# glowbs_5.net
KiCad netlist of a schematic drawn in EAGLE
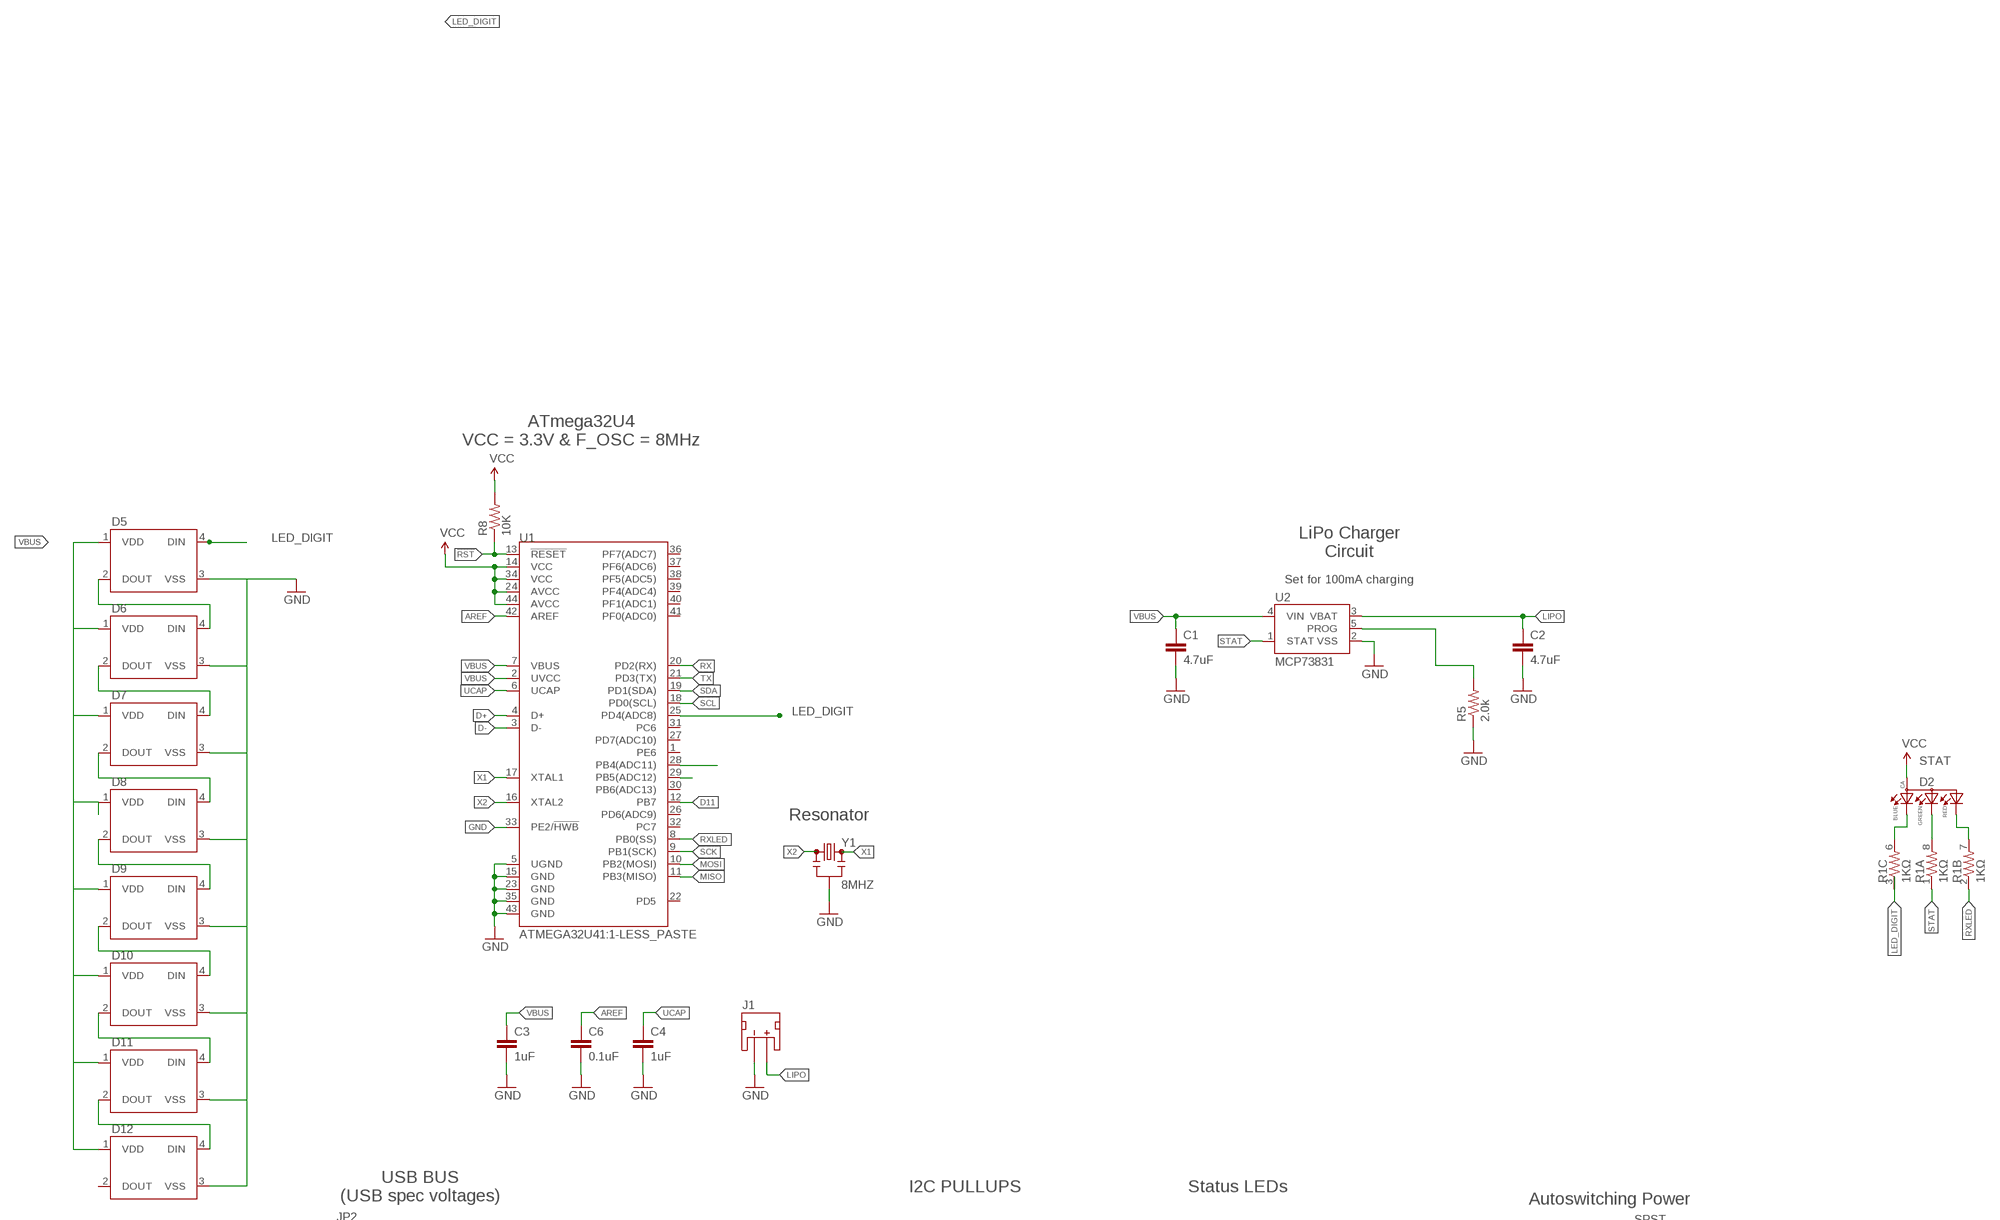
[diagram p0: schematic, sheet 1, part 1 of 2]
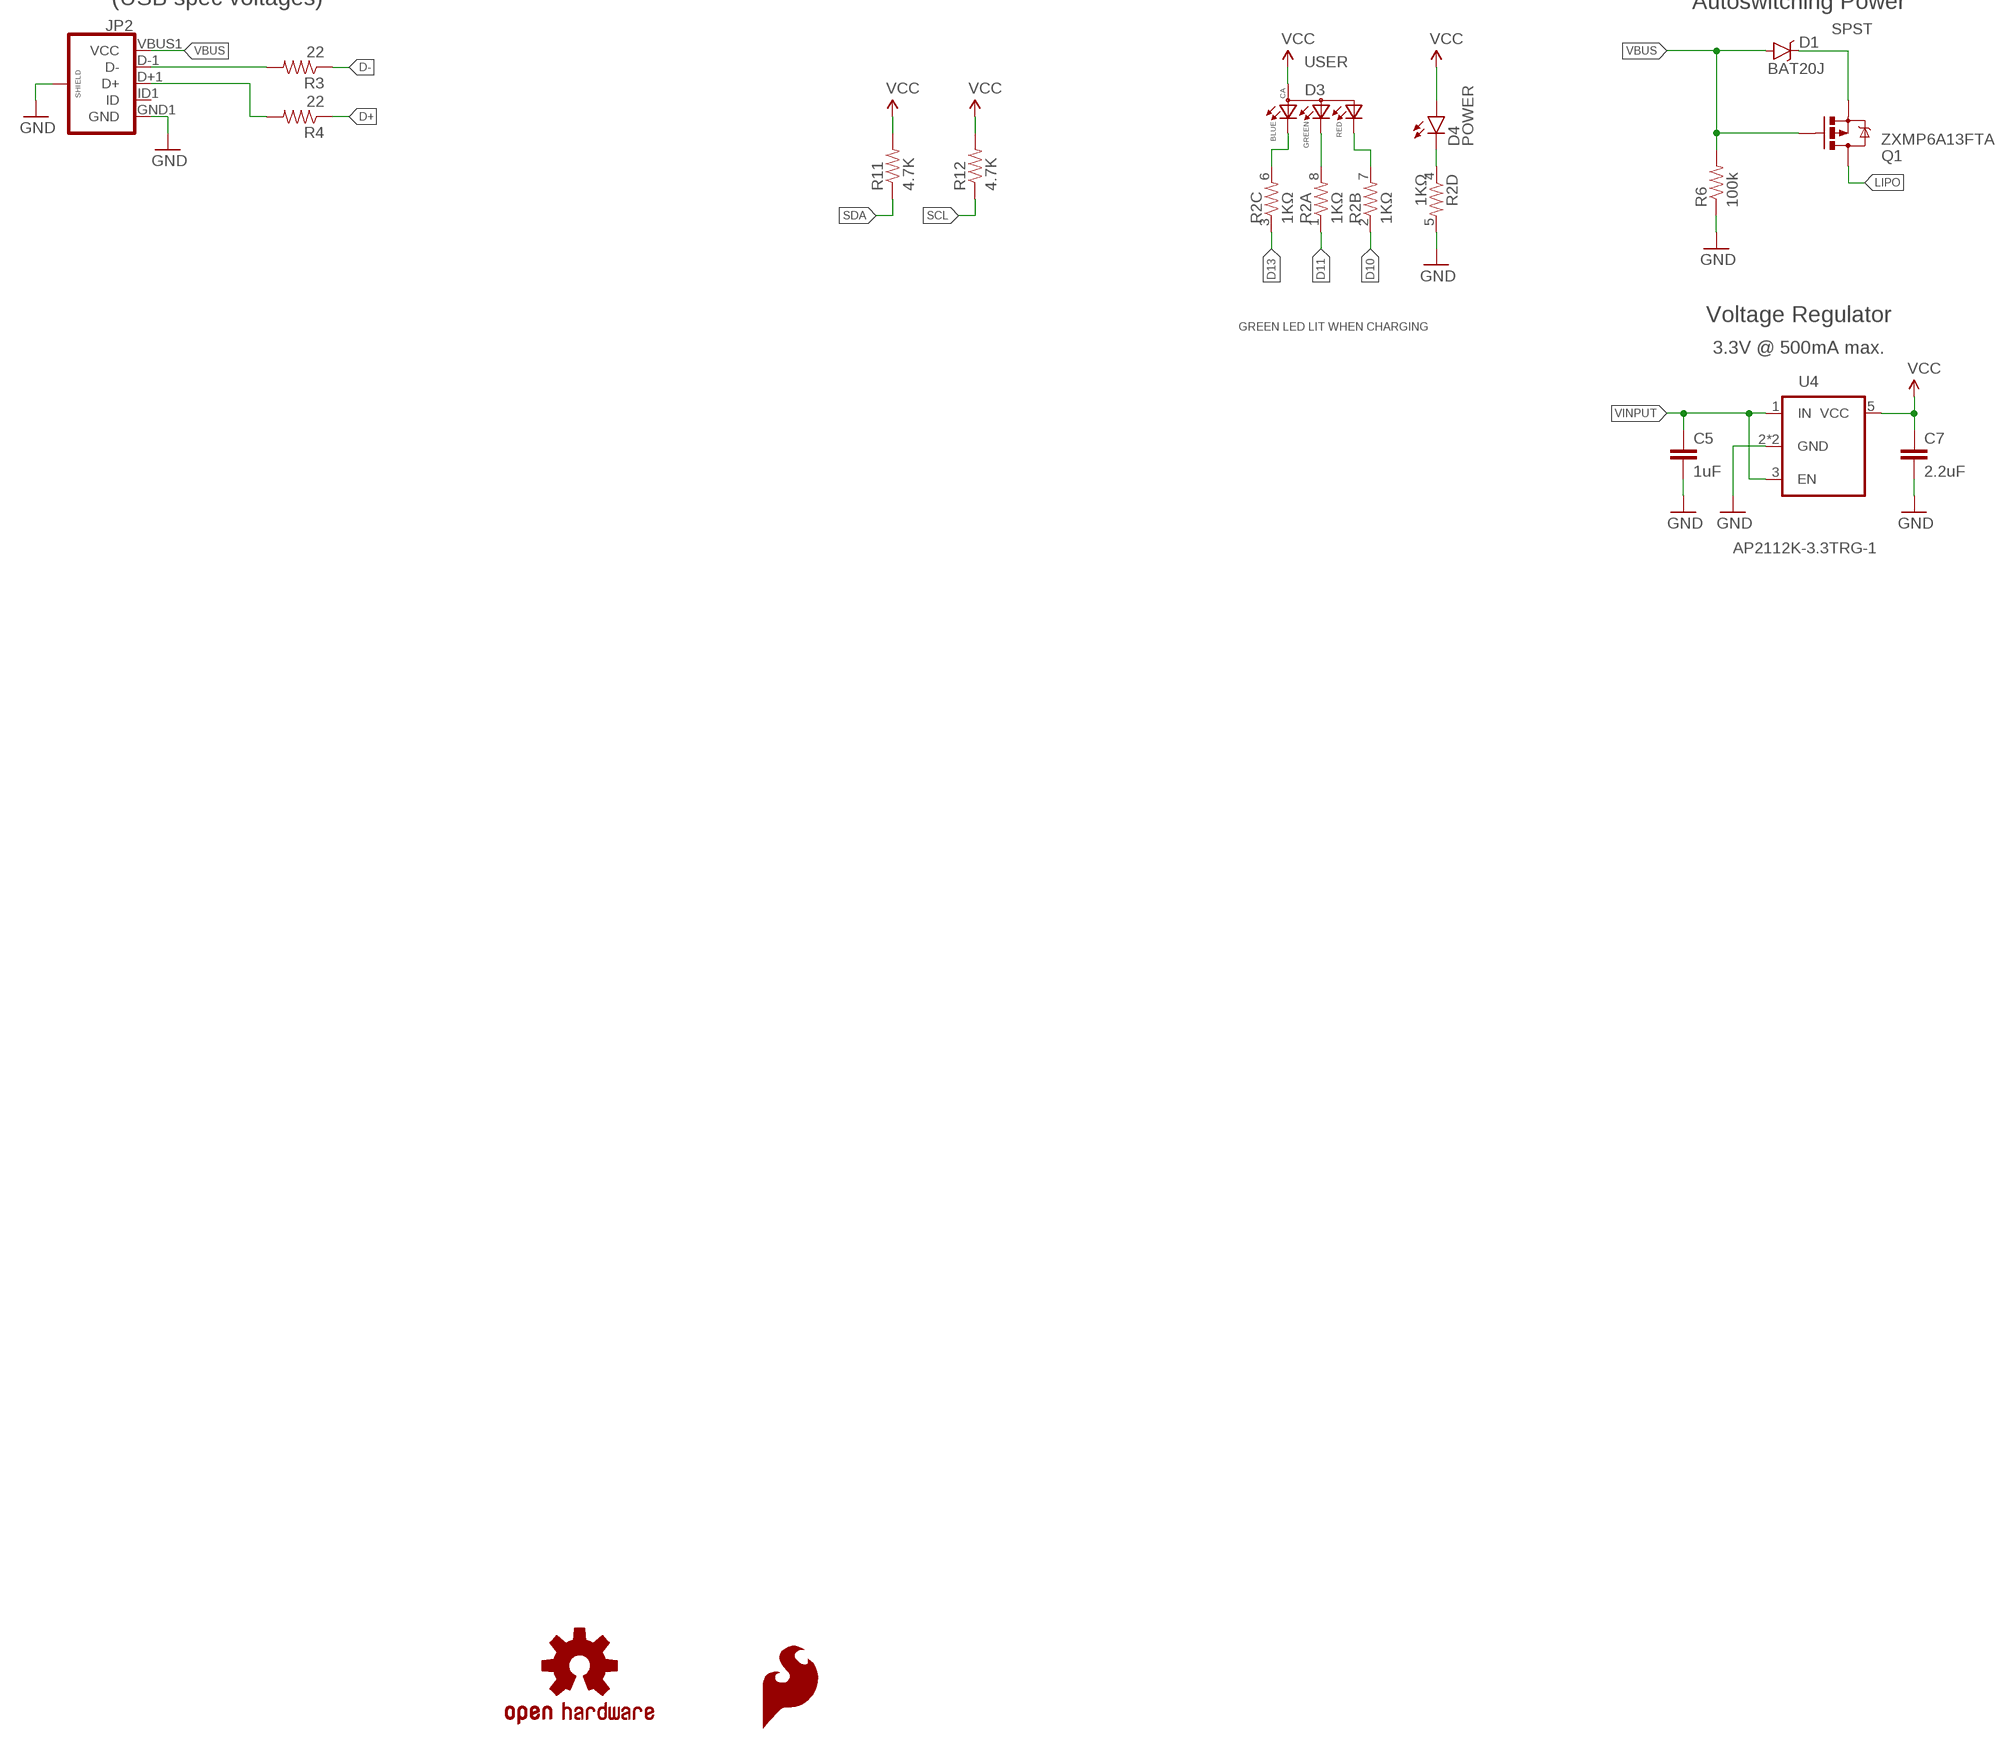
[diagram p1: schematic, sheet 1, part 2 of 2]

(export (version "E")
  (design (tool "Eeschema 10.0.6"))
  (components
    (comp (ref "C1")
      (value "4.7uF")
      (footprint "eagle-import:0603-CAP")
      (libsource (lib "eagle-import") (part "CAP0603-CAP"))
    )
    (comp (ref "C2")
      (value "4.7uF")
      (footprint "eagle-import:0603-CAP")
      (libsource (lib "eagle-import") (part "CAP0603-CAP"))
    )
    (comp (ref "C3")
      (value "1uF")
      (footprint "eagle-import:0603-CAP")
      (libsource (lib "eagle-import") (part "CAP0603-CAP"))
    )
    (comp (ref "C4")
      (value "1uF")
      (footprint "eagle-import:0603-CAP")
      (libsource (lib "eagle-import") (part "CAP0603-CAP"))
    )
    (comp (ref "C5")
      (value "1uF")
      (footprint "eagle-import:0603-CAP")
      (libsource (lib "eagle-import") (part "CAP0603-CAP"))
    )
    (comp (ref "C6")
      (value "0.1uF")
      (footprint "eagle-import:0603-CAP")
      (libsource (lib "eagle-import") (part "0.1UF-25V(+80/-20%)(0603)"))
    )
    (comp (ref "C7")
      (value "2.2uF")
      (footprint "eagle-import:0603-CAP")
      (libsource (lib "eagle-import") (part "2.2UF-10V-20%(0603)"))
    )
    (comp (ref "D1")
      (value "BAT20J")
      (footprint "eagle-import:SOD-323")
      (libsource (lib "eagle-import") (part "DIODE-SCHOTTKY-BAT20J"))
    )
    (comp (ref "D2")
      (value "0.13_RGB_LEDPLCC")
      (footprint "eagle-import:P-LCC-4-3")
      (fields (field (name "PROD_ID") "DIO-12986"))
      (libsource (lib "eagle-import") (part "0.13_RGB_LEDPLCC"))
    )
    (comp (ref "D3")
      (value "0.13_RGB_LEDPLCC")
      (footprint "eagle-import:P-LCC-4-3")
      (libsource (lib "eagle-import") (part "0.13_RGB_LEDPLCC"))
    )
    (comp (ref "D4")
      (value "POWER")
      (footprint "eagle-import:LED-0603")
      (fields (field (name "PROD_ID") "DIO-00821"))
      (libsource (lib "eagle-import") (part "LED-GREEN0603"))
    )
    (comp (ref "D5")
      (value "WS2812B")
      (footprint "eagle-import:WS2812B")
      (libsource (lib "eagle-import") (part "WS2812B"))
    )
    (comp (ref "D6")
      (value "WS2812B")
      (footprint "eagle-import:WS2812B")
      (libsource (lib "eagle-import") (part "WS2812B"))
    )
    (comp (ref "D7")
      (value "WS2812B")
      (footprint "eagle-import:WS2812B")
      (libsource (lib "eagle-import") (part "WS2812B"))
    )
    (comp (ref "D8")
      (value "WS2812B")
      (footprint "eagle-import:WS2812B")
      (libsource (lib "eagle-import") (part "WS2812B"))
    )
    (comp (ref "D9")
      (value "WS2812B")
      (footprint "eagle-import:WS2812B")
      (libsource (lib "eagle-import") (part "WS2812B"))
    )
    (comp (ref "D10")
      (value "WS2812B")
      (footprint "eagle-import:WS2812B")
      (libsource (lib "eagle-import") (part "WS2812B"))
    )
    (comp (ref "D11")
      (value "WS2812B")
      (footprint "eagle-import:WS2812B")
      (libsource (lib "eagle-import") (part "WS2812B"))
    )
    (comp (ref "D12")
      (value "WS2812B")
      (footprint "eagle-import:WS2812B")
      (libsource (lib "eagle-import") (part "WS2812B"))
    )
    (comp (ref "J1")
      (value "LiPo")
      (footprint "eagle-import:JST-2-SMD")
      (libsource (lib "eagle-import") (part "JST_2MM_MALE"))
    )
    (comp (ref "JP2")
      (value "USB_MICROB_PLUGCONN-11752")
      (footprint "eagle-import:USB-B-MICRO-SMD_V03")
      (libsource (lib "eagle-import") (part "USB_MICROB_PLUGCONN-11752"))
    )
    (comp (ref "LOGO1")
      (value "OSHW-LOGOS")
      (footprint "eagle-import:OSHW-LOGO-S")
      (libsource (lib "eagle-import") (part "OSHW-LOGOS"))
    )
    (comp (ref "LOGO2")
      (value "SFE_LOGO_FLAME.1_INCH")
      (footprint "eagle-import:SFE_LOGO_FLAME_.1")
      (libsource (lib "eagle-import") (part "SFE_LOGO_FLAME.1_INCH"))
    )
    (comp (ref "Q1")
      (value "ZXMP6A13FTA")
      (footprint "eagle-import:SOT23-3")
      (libsource (lib "eagle-import") (part "MOSFET-PCHANNEL"))
    )
    (comp (ref "R1")
      (value "1KΩ")
      (footprint "eagle-import:0603-ARV")
      (fields (field (name "PROD_ID") "RES-12985"))
      (libsource (lib "eagle-import") (part "RESISTOR-ARRAY0603-ARV"))
    )
    (comp (ref "R2")
      (value "1KΩ")
      (footprint "eagle-import:0603-ARV")
      (fields (field (name "PROD_ID") "RES-12985"))
      (libsource (lib "eagle-import") (part "RESISTOR-ARRAY0603-ARV"))
    )
    (comp (ref "R3")
      (value "22")
      (footprint "eagle-import:0603-RES")
      (libsource (lib "eagle-import") (part "RESISTOR0603"))
    )
    (comp (ref "R4")
      (value "22")
      (footprint "eagle-import:0603-RES")
      (libsource (lib "eagle-import") (part "RESISTOR0603"))
    )
    (comp (ref "R5")
      (value "2.0k")
      (footprint "eagle-import:0603-RES")
      (libsource (lib "eagle-import") (part "2.0KOHM1/10W5%(0603)"))
    )
    (comp (ref "R6")
      (value "100k")
      (footprint "eagle-import:0603-RES")
      (libsource (lib "eagle-import") (part "100KOHM-1/10W-1%(0603)"))
    )
    (comp (ref "R8")
      (value "10K")
      (footprint "eagle-import:0603-RES")
      (libsource (lib "eagle-import") (part "10KOHM-1/10W-1%(0603)0603"))
    )
    (comp (ref "R11")
      (value "4.7K")
      (footprint "eagle-import:0603-RES")
      (libsource (lib "eagle-import") (part "RESISTOR0603-RES"))
    )
    (comp (ref "R12")
      (value "4.7K")
      (footprint "eagle-import:0603-RES")
      (libsource (lib "eagle-import") (part "RESISTOR0603-RES"))
    )
    (comp (ref "U1")
      (value "ATMEGA32U41:1-LESS_PASTE")
      (footprint "eagle-import:QFN-44-NOPAD_1_1-LESS_PASTE")
      (libsource (lib "eagle-import") (part "ATMEGA32U41{colon}1-LESS_PASTE"))
    )
    (comp (ref "U2")
      (value "MCP73831")
      (footprint "eagle-import:SOT23-5")
      (libsource (lib "eagle-import") (part "MCP73831"))
    )
    (comp (ref "U4")
      (value "AP2112K-3.3TRG-1")
      (footprint "eagle-import:SOT23-5")
      (libsource (lib "eagle-import") (part "LDO-TPS78233"))
    )
    (comp (ref "Y1")
      (value "8MHZ")
      (footprint "eagle-import:RESONATOR-SMD")
      (libsource (lib "eagle-import") (part "RESONATOR8MHZ"))
    )
  )
  (nets
    (net (code "1") (name "/~{RST}") (class "Default")
      (node (ref "R8") (pin "1") (pinfunction "1_1") (pintype "passive"))
      (node (ref "U1") (pin "13") (pinfunction "~{RESET}_13") (pintype "bidirectional"))
    )
    (net (code "2") (name "AREF") (class "Default")
      (node (ref "C6") (pin "1") (pinfunction "1_1") (pintype "passive"))
      (node (ref "U1") (pin "42") (pinfunction "AREF_42") (pintype "bidirectional"))
    )
    (net (code "3") (name "D+") (class "Default")
      (node (ref "R4") (pin "1") (pinfunction "1_1") (pintype "passive"))
      (node (ref "U1") (pin "4") (pinfunction "D+_4") (pintype "bidirectional"))
    )
    (net (code "4") (name "D-") (class "Default")
      (node (ref "R3") (pin "1") (pinfunction "1_1") (pintype "passive"))
      (node (ref "U1") (pin "3") (pinfunction "D-_3") (pintype "bidirectional"))
    )
    (net (code "5") (name "D10") (class "Default")
      (node (ref "R2") (pin "2") (pinfunction "1_2") (pintype "passive"))
    )
    (net (code "6") (name "D11") (class "Default")
      (node (ref "R2") (pin "1") (pinfunction "1_1") (pintype "passive"))
      (node (ref "U1") (pin "12") (pinfunction "PB7_12") (pintype "bidirectional"))
    )
    (net (code "7") (name "D13") (class "Default")
      (node (ref "R2") (pin "3") (pinfunction "1_3") (pintype "passive"))
    )
    (net (code "8") (name "GND") (class "Default")
      (node (ref "C1") (pin "2") (pinfunction "2_2") (pintype "passive"))
      (node (ref "C2") (pin "2") (pinfunction "2_2") (pintype "passive"))
      (node (ref "C3") (pin "2") (pinfunction "2_2") (pintype "passive"))
      (node (ref "C4") (pin "2") (pinfunction "2_2") (pintype "passive"))
      (node (ref "C5") (pin "2") (pinfunction "2_2") (pintype "passive"))
      (node (ref "C6") (pin "2") (pinfunction "2_2") (pintype "passive"))
      (node (ref "C7") (pin "2") (pinfunction "2_2") (pintype "passive"))
      (node (ref "D10") (pin "3") (pinfunction "VSS_3") (pintype "power_in"))
      (node (ref "D11") (pin "3") (pinfunction "VSS_3") (pintype "power_in"))
      (node (ref "D12") (pin "3") (pinfunction "VSS_3") (pintype "power_in"))
      (node (ref "D5") (pin "3") (pinfunction "VSS_3") (pintype "power_in"))
      (node (ref "D6") (pin "3") (pinfunction "VSS_3") (pintype "power_in"))
      (node (ref "D7") (pin "3") (pinfunction "VSS_3") (pintype "power_in"))
      (node (ref "D8") (pin "3") (pinfunction "VSS_3") (pintype "power_in"))
      (node (ref "D9") (pin "3") (pinfunction "VSS_3") (pintype "power_in"))
      (node (ref "J1") (pin "1") (pinfunction "-_1") (pintype "bidirectional"))
      (node (ref "JP2") (pin "GND1") (pinfunction "GND_GND1") (pintype "bidirectional"))
      (node (ref "JP2") (pin "SHIELD1") (pinfunction "SHIELD_SHIELD1") (pintype "bidirectional"))
      (node (ref "JP2") (pin "SHIELD2") (pinfunction "SHIELD_SHIELD2") (pintype "bidirectional"))
      (node (ref "JP2") (pin "SHIELD3") (pinfunction "SHIELD_SHIELD3") (pintype "bidirectional"))
      (node (ref "R2") (pin "5") (pinfunction "2_5") (pintype "passive"))
      (node (ref "R5") (pin "1") (pinfunction "1_1") (pintype "passive"))
      (node (ref "R6") (pin "1") (pinfunction "1_1") (pintype "passive"))
      (node (ref "U1") (pin "15") (pinfunction "GND_15") (pintype "bidirectional"))
      (node (ref "U1") (pin "23") (pinfunction "GND_23") (pintype "bidirectional"))
      (node (ref "U1") (pin "33") (pinfunction "PE2/~{HWB}_33") (pintype "bidirectional"))
      (node (ref "U1") (pin "35") (pinfunction "GND_35") (pintype "bidirectional"))
      (node (ref "U1") (pin "43") (pinfunction "GND_43") (pintype "bidirectional"))
      (node (ref "U1") (pin "5") (pinfunction "UGND_5") (pintype "bidirectional"))
      (node (ref "U2") (pin "2") (pinfunction "VSS_2") (pintype "power_in"))
      (node (ref "U4") (pin "2") (pinfunction "GND_2") (pintype "input"))
      (node (ref "U4") (pin "4") (pinfunction "GND_4") (pintype "input"))
      (node (ref "Y1") (pin "2") (pinfunction "2_2") (pintype "passive"))
    )
    (net (code "9") (name "LED_DIGIT") (class "Default")
      (node (ref "D5") (pin "4") (pinfunction "DIN_4") (pintype "input"))
      (node (ref "R1") (pin "3") (pinfunction "1_3") (pintype "passive"))
      (node (ref "U1") (pin "25") (pinfunction "PD4(ADC8)_25") (pintype "bidirectional"))
    )
    (net (code "10") (name "LIPO") (class "Default")
      (node (ref "C2") (pin "1") (pinfunction "1_1") (pintype "passive"))
      (node (ref "J1") (pin "2") (pinfunction "+_2") (pintype "bidirectional"))
      (node (ref "Q1") (pin "3") (pinfunction "D_3") (pintype "passive"))
      (node (ref "U2") (pin "3") (pinfunction "VBAT_3") (pintype "power_in"))
    )
    (net (code "11") (name "MISO") (class "Default")
      (node (ref "U1") (pin "11") (pinfunction "PB3(MISO)_11") (pintype "bidirectional"))
    )
    (net (code "12") (name "MOSI") (class "Default")
      (node (ref "U1") (pin "10") (pinfunction "PB2(MOSI)_10") (pintype "bidirectional"))
    )
    (net (code "13") (name "Net-(D2-BLUE)") (class "Default")
      (node (ref "D2") (pin "3") (pinfunction "BLUE_3") (pintype "passive"))
      (node (ref "R1") (pin "6") (pinfunction "2_6") (pintype "passive"))
    )
    (net (code "14") (name "Net-(D2-GREEN)") (class "Default")
      (node (ref "D2") (pin "2") (pinfunction "GREEN_2") (pintype "passive"))
      (node (ref "R1") (pin "8") (pinfunction "2_8") (pintype "passive"))
    )
    (net (code "15") (name "Net-(D2-RED)") (class "Default")
      (node (ref "D2") (pin "1") (pinfunction "RED_1") (pintype "passive"))
      (node (ref "R1") (pin "7") (pinfunction "2_7") (pintype "passive"))
    )
    (net (code "16") (name "Net-(D3-BLUE)") (class "Default")
      (node (ref "D3") (pin "3") (pinfunction "BLUE_3") (pintype "passive"))
      (node (ref "R2") (pin "6") (pinfunction "2_6") (pintype "passive"))
    )
    (net (code "17") (name "Net-(D3-GREEN)") (class "Default")
      (node (ref "D3") (pin "2") (pinfunction "GREEN_2") (pintype "passive"))
      (node (ref "R2") (pin "8") (pinfunction "2_8") (pintype "passive"))
    )
    (net (code "18") (name "Net-(D3-RED)") (class "Default")
      (node (ref "D3") (pin "1") (pinfunction "RED_1") (pintype "passive"))
      (node (ref "R2") (pin "7") (pinfunction "2_7") (pintype "passive"))
    )
    (net (code "19") (name "Net-(D5-DOUT)") (class "Default")
      (node (ref "D5") (pin "2") (pinfunction "DOUT_2") (pintype "output"))
      (node (ref "D6") (pin "4") (pinfunction "DIN_4") (pintype "input"))
    )
    (net (code "20") (name "Net-(D6-DOUT)") (class "Default")
      (node (ref "D6") (pin "2") (pinfunction "DOUT_2") (pintype "output"))
      (node (ref "D7") (pin "4") (pinfunction "DIN_4") (pintype "input"))
    )
    (net (code "21") (name "Net-(D7-DOUT)") (class "Default")
      (node (ref "D7") (pin "2") (pinfunction "DOUT_2") (pintype "output"))
      (node (ref "D8") (pin "4") (pinfunction "DIN_4") (pintype "input"))
    )
    (net (code "22") (name "Net-(D8-DOUT)") (class "Default")
      (node (ref "D8") (pin "2") (pinfunction "DOUT_2") (pintype "output"))
      (node (ref "D9") (pin "4") (pinfunction "DIN_4") (pintype "input"))
    )
    (net (code "23") (name "Net-(D10-DIN)") (class "Default")
      (node (ref "D10") (pin "4") (pinfunction "DIN_4") (pintype "input"))
      (node (ref "D9") (pin "2") (pinfunction "DOUT_2") (pintype "output"))
    )
    (net (code "24") (name "Net-(D10-DOUT)") (class "Default")
      (node (ref "D10") (pin "2") (pinfunction "DOUT_2") (pintype "output"))
      (node (ref "D11") (pin "4") (pinfunction "DIN_4") (pintype "input"))
    )
    (net (code "25") (name "Net-(D11-DOUT)") (class "Default")
      (node (ref "D11") (pin "2") (pinfunction "DOUT_2") (pintype "output"))
      (node (ref "D12") (pin "4") (pinfunction "DIN_4") (pintype "input"))
    )
    (net (code "26") (name "Net-(JP2-D+)") (class "Default")
      (node (ref "JP2") (pin "D+1") (pinfunction "D+_D+1") (pintype "bidirectional"))
      (node (ref "R4") (pin "2") (pinfunction "2_2") (pintype "passive"))
    )
    (net (code "27") (name "Net-(JP2-D-)") (class "Default")
      (node (ref "JP2") (pin "D-1") (pinfunction "D-_D-1") (pintype "bidirectional"))
      (node (ref "R3") (pin "2") (pinfunction "2_2") (pintype "passive"))
    )
    (net (code "28") (name "Net-(Q1-S)") (class "Default")
      (node (ref "D1") (pin "C") (pinfunction "C_C") (pintype "passive"))
      (node (ref "Q1") (pin "2") (pinfunction "S_2") (pintype "passive"))
    )
    (net (code "29") (name "Net-(R2D-1)") (class "Default")
      (node (ref "D4") (pin "C") (pinfunction "C_C") (pintype "passive"))
      (node (ref "R2") (pin "4") (pinfunction "1_4") (pintype "passive"))
    )
    (net (code "30") (name "Net-(U2-PROG)") (class "Default")
      (node (ref "R5") (pin "2") (pinfunction "2_2") (pintype "passive"))
      (node (ref "U2") (pin "5") (pinfunction "PROG_5") (pintype "input"))
    )
    (net (code "31") (name "RX") (class "Default")
      (node (ref "U1") (pin "20") (pinfunction "PD2(RX)_20") (pintype "bidirectional"))
    )
    (net (code "32") (name "RXLED") (class "Default")
      (node (ref "R1") (pin "2") (pinfunction "1_2") (pintype "passive"))
      (node (ref "U1") (pin "8") (pinfunction "PB0(SS)_8") (pintype "bidirectional"))
    )
    (net (code "33") (name "SCK") (class "Default")
      (node (ref "U1") (pin "9") (pinfunction "PB1(SCK)_9") (pintype "bidirectional"))
    )
    (net (code "34") (name "SCL") (class "Default")
      (node (ref "R12") (pin "1") (pinfunction "1_1") (pintype "passive"))
      (node (ref "U1") (pin "18") (pinfunction "PD0(SCL)_18") (pintype "bidirectional"))
    )
    (net (code "35") (name "SDA") (class "Default")
      (node (ref "R11") (pin "1") (pinfunction "1_1") (pintype "passive"))
      (node (ref "U1") (pin "19") (pinfunction "PD1(SDA)_19") (pintype "bidirectional"))
    )
    (net (code "36") (name "STAT") (class "Default")
      (node (ref "R1") (pin "1") (pinfunction "1_1") (pintype "passive"))
      (node (ref "U2") (pin "1") (pinfunction "STAT_1") (pintype "output"))
    )
    (net (code "37") (name "TX") (class "Default")
      (node (ref "U1") (pin "21") (pinfunction "PD3(TX)_21") (pintype "bidirectional"))
    )
    (net (code "38") (name "UCAP") (class "Default")
      (node (ref "C4") (pin "1") (pinfunction "1_1") (pintype "passive"))
      (node (ref "U1") (pin "6") (pinfunction "UCAP_6") (pintype "bidirectional"))
    )
    (net (code "39") (name "VBUS") (class "Default")
      (node (ref "C1") (pin "1") (pinfunction "1_1") (pintype "passive"))
      (node (ref "C3") (pin "1") (pinfunction "1_1") (pintype "passive"))
      (node (ref "D1") (pin "A") (pinfunction "A_A") (pintype "passive"))
      (node (ref "D10") (pin "1") (pinfunction "VDD_1") (pintype "power_in"))
      (node (ref "D11") (pin "1") (pinfunction "VDD_1") (pintype "power_in"))
      (node (ref "D12") (pin "1") (pinfunction "VDD_1") (pintype "power_in"))
      (node (ref "D5") (pin "1") (pinfunction "VDD_1") (pintype "power_in"))
      (node (ref "D6") (pin "1") (pinfunction "VDD_1") (pintype "power_in"))
      (node (ref "D7") (pin "1") (pinfunction "VDD_1") (pintype "power_in"))
      (node (ref "D8") (pin "1") (pinfunction "VDD_1") (pintype "power_in"))
      (node (ref "D9") (pin "1") (pinfunction "VDD_1") (pintype "power_in"))
      (node (ref "JP2") (pin "VBUS1") (pinfunction "VCC_VBUS1") (pintype "bidirectional"))
      (node (ref "Q1") (pin "1") (pinfunction "G_1") (pintype "passive"))
      (node (ref "R6") (pin "2") (pinfunction "2_2") (pintype "passive"))
      (node (ref "U1") (pin "2") (pinfunction "UVCC_2") (pintype "bidirectional"))
      (node (ref "U1") (pin "7") (pinfunction "VBUS_7") (pintype "bidirectional"))
      (node (ref "U2") (pin "4") (pinfunction "VIN_4") (pintype "power_in"))
    )
    (net (code "40") (name "VCC") (class "Default")
      (node (ref "C7") (pin "1") (pinfunction "1_1") (pintype "passive"))
      (node (ref "D2") (pin "4") (pinfunction "ANODE_4") (pintype "passive"))
      (node (ref "D3") (pin "4") (pinfunction "ANODE_4") (pintype "passive"))
      (node (ref "D4") (pin "A") (pinfunction "A_A") (pintype "passive"))
      (node (ref "R11") (pin "2") (pinfunction "2_2") (pintype "passive"))
      (node (ref "R12") (pin "2") (pinfunction "2_2") (pintype "passive"))
      (node (ref "R8") (pin "2") (pinfunction "2_2") (pintype "passive"))
      (node (ref "U1") (pin "14") (pinfunction "VCC_14") (pintype "bidirectional"))
      (node (ref "U1") (pin "24") (pinfunction "AVCC_24") (pintype "bidirectional"))
      (node (ref "U1") (pin "34") (pinfunction "VCC_34") (pintype "bidirectional"))
      (node (ref "U1") (pin "44") (pinfunction "AVCC_44") (pintype "bidirectional"))
      (node (ref "U4") (pin "5") (pinfunction "VCC_5") (pintype "power_in"))
    )
    (net (code "41") (name "VINPUT") (class "Default")
      (node (ref "C5") (pin "1") (pinfunction "1_1") (pintype "passive"))
      (node (ref "U4") (pin "1") (pinfunction "IN_1") (pintype "input"))
      (node (ref "U4") (pin "3") (pinfunction "EN_3") (pintype "input"))
    )
    (net (code "42") (name "X1") (class "Default")
      (node (ref "U1") (pin "17") (pinfunction "XTAL1_17") (pintype "bidirectional"))
      (node (ref "Y1") (pin "3") (pinfunction "3_3") (pintype "passive"))
    )
    (net (code "43") (name "X2") (class "Default")
      (node (ref "U1") (pin "16") (pinfunction "XTAL2_16") (pintype "bidirectional"))
      (node (ref "Y1") (pin "1") (pinfunction "1_1") (pintype "passive"))
    )
    (net (code "44") (name "unconnected-(D12-DOUT-Pad2)") (class "Default")
      (node (ref "D12") (pin "2") (pinfunction "DOUT_2") (pintype "output"))
    )
    (net (code "45") (name "unconnected-(J1-PAD1-PadNC1)") (class "Default")
      (node (ref "J1") (pin "NC1") (pinfunction "PAD1_NC1") (pintype "bidirectional"))
    )
    (net (code "46") (name "unconnected-(J1-PAD2-PadNC2)") (class "Default")
      (node (ref "J1") (pin "NC2") (pinfunction "PAD2_NC2") (pintype "bidirectional"))
    )
    (net (code "47") (name "unconnected-(JP2-ID-PadID1)") (class "Default")
      (node (ref "JP2") (pin "ID1") (pinfunction "ID_ID1") (pintype "bidirectional"))
    )
    (net (code "48") (name "unconnected-(U1-PB4(ADC11)-Pad28)") (class "Default")
      (node (ref "U1") (pin "28") (pinfunction "PB4(ADC11)_28") (pintype "bidirectional"))
    )
    (net (code "49") (name "unconnected-(U1-PB5(ADC12)-Pad29)") (class "Default")
      (node (ref "U1") (pin "29") (pinfunction "PB5(ADC12)_29") (pintype "bidirectional"))
    )
    (net (code "50") (name "unconnected-(U1-PB6(ADC13)-Pad30)") (class "Default")
      (node (ref "U1") (pin "30") (pinfunction "PB6(ADC13)_30") (pintype "bidirectional"))
    )
    (net (code "51") (name "unconnected-(U1-PC6-Pad31)") (class "Default")
      (node (ref "U1") (pin "31") (pinfunction "PC6_31") (pintype "bidirectional"))
    )
    (net (code "52") (name "unconnected-(U1-PC7-Pad32)") (class "Default")
      (node (ref "U1") (pin "32") (pinfunction "PC7_32") (pintype "bidirectional"))
    )
    (net (code "53") (name "unconnected-(U1-PD5-Pad22)") (class "Default")
      (node (ref "U1") (pin "22") (pinfunction "PD5_22") (pintype "bidirectional"))
    )
    (net (code "54") (name "unconnected-(U1-PD6(ADC9)-Pad26)") (class "Default")
      (node (ref "U1") (pin "26") (pinfunction "PD6(ADC9)_26") (pintype "bidirectional"))
    )
    (net (code "55") (name "unconnected-(U1-PD7(ADC10)-Pad27)") (class "Default")
      (node (ref "U1") (pin "27") (pinfunction "PD7(ADC10)_27") (pintype "bidirectional"))
    )
    (net (code "56") (name "unconnected-(U1-PE6-Pad1)") (class "Default")
      (node (ref "U1") (pin "1") (pinfunction "PE6_1") (pintype "bidirectional"))
    )
    (net (code "57") (name "unconnected-(U1-PF0(ADC0)-Pad41)") (class "Default")
      (node (ref "U1") (pin "41") (pinfunction "PF0(ADC0)_41") (pintype "bidirectional"))
    )
    (net (code "58") (name "unconnected-(U1-PF1(ADC1)-Pad40)") (class "Default")
      (node (ref "U1") (pin "40") (pinfunction "PF1(ADC1)_40") (pintype "bidirectional"))
    )
    (net (code "59") (name "unconnected-(U1-PF4(ADC4)-Pad39)") (class "Default")
      (node (ref "U1") (pin "39") (pinfunction "PF4(ADC4)_39") (pintype "bidirectional"))
    )
    (net (code "60") (name "unconnected-(U1-PF5(ADC5)-Pad38)") (class "Default")
      (node (ref "U1") (pin "38") (pinfunction "PF5(ADC5)_38") (pintype "bidirectional"))
    )
    (net (code "61") (name "unconnected-(U1-PF6(ADC6)-Pad37)") (class "Default")
      (node (ref "U1") (pin "37") (pinfunction "PF6(ADC6)_37") (pintype "bidirectional"))
    )
    (net (code "62") (name "unconnected-(U1-PF7(ADC7)-Pad36)") (class "Default")
      (node (ref "U1") (pin "36") (pinfunction "PF7(ADC7)_36") (pintype "bidirectional"))
    )
  )
)
